# sleep_light.net
KiCad netlist of a schematic drawn in EAGLE
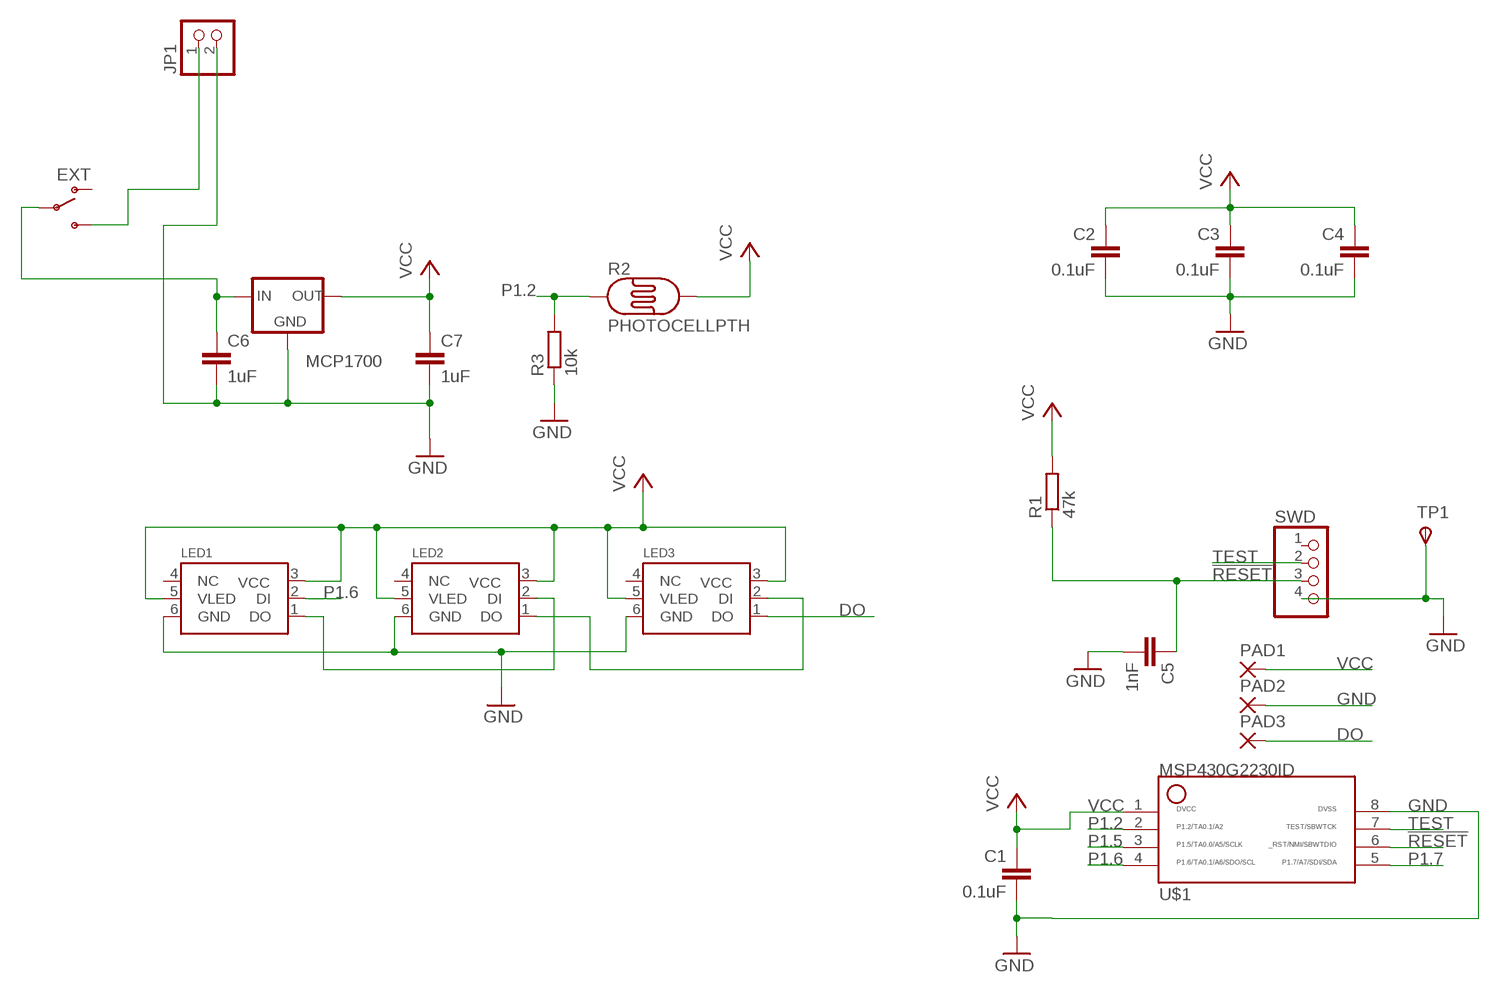
[diagram p0: schematic, sheet 1]

(export (version "E")
  (design (tool "Eeschema 10.0.6"))
  (components
    (comp (ref "C1")
      (value "0.1uF")
      (footprint "eagle-import:C0805")
      (libsource (lib "eagle-import") (part "C-EUC0805"))
    )
    (comp (ref "C2")
      (value "0.1uF")
      (footprint "eagle-import:C0805")
      (libsource (lib "eagle-import") (part "C-EUC0805"))
    )
    (comp (ref "C3")
      (value "0.1uF")
      (footprint "eagle-import:C0805")
      (libsource (lib "eagle-import") (part "C-EUC0805"))
    )
    (comp (ref "C4")
      (value "0.1uF")
      (footprint "eagle-import:C0805")
      (libsource (lib "eagle-import") (part "C-EUC0805"))
    )
    (comp (ref "C5")
      (value "1nF")
      (footprint "eagle-import:C0805")
      (libsource (lib "eagle-import") (part "C-EUC0805"))
    )
    (comp (ref "C6")
      (value "1uF")
      (footprint "eagle-import:C0805")
      (libsource (lib "eagle-import") (part "C-EUC0805"))
    )
    (comp (ref "C7")
      (value "1uF")
      (footprint "eagle-import:C0805")
      (libsource (lib "eagle-import") (part "C-EUC0805"))
    )
    (comp (ref "JP1")
      (value "PINHD-1X2")
      (footprint "eagle-import:1X02")
      (libsource (lib "eagle-import") (part "PINHD-1X2"))
    )
    (comp (ref "LED1")
      (value "5050WS2811W")
      (footprint "eagle-import:RGBLED5050W")
      (libsource (lib "eagle-import") (part "5050WS2811W"))
    )
    (comp (ref "LED2")
      (value "5050WS2811W")
      (footprint "eagle-import:RGBLED5050W")
      (libsource (lib "eagle-import") (part "5050WS2811W"))
    )
    (comp (ref "LED3")
      (value "5050WS2811W")
      (footprint "eagle-import:RGBLED5050W")
      (libsource (lib "eagle-import") (part "5050WS2811W"))
    )
    (comp (ref "MCP1700")
      (value "MCP1700")
      (footprint "eagle-import:SOT-23")
      (libsource (lib "eagle-import") (part "MCP1700SOT-23"))
    )
    (comp (ref "ON")
      (value "EXT")
      (footprint "eagle-import:SWITCH-SPDT")
      (libsource (lib "eagle-import") (part "SWITCH-SPSTPTH"))
    )
    (comp (ref "PAD1")
      (value "SMD2")
      (footprint "eagle-import:SMD1,27-2,54")
      (libsource (lib "eagle-import") (part "SMD2"))
    )
    (comp (ref "PAD2")
      (value "SMD2")
      (footprint "eagle-import:SMD1,27-2,54")
      (libsource (lib "eagle-import") (part "SMD2"))
    )
    (comp (ref "PAD3")
      (value "SMD2")
      (footprint "eagle-import:SMD1,27-2,54")
      (libsource (lib "eagle-import") (part "SMD2"))
    )
    (comp (ref "R1")
      (value "47k")
      (footprint "eagle-import:R0805")
      (libsource (lib "eagle-import") (part "R-EU_R0805"))
    )
    (comp (ref "R2")
      (value "PHOTOCELLPTH")
      (footprint "eagle-import:PHOTOCELL")
      (libsource (lib "eagle-import") (part "PHOTOCELLPTH"))
    )
    (comp (ref "R3")
      (value "10k")
      (footprint "eagle-import:R0805")
      (libsource (lib "eagle-import") (part "R-EU_R0805"))
    )
    (comp (ref "SWD")
      (value "PINHD-1X4")
      (footprint "eagle-import:1X04")
      (libsource (lib "eagle-import") (part "PINHD-1X4"))
    )
    (comp (ref "TP1")
      (value "TPSTP20R")
      (footprint "eagle-import:TP20R")
      (libsource (lib "eagle-import") (part "TPSTP20R"))
    )
    (comp (ref "U$1")
      (value "MSP430G2230ID")
      (footprint "eagle-import:SO08")
      (libsource (lib "eagle-import") (part "MSP430G2230ID"))
    )
  )
  (nets
    (net (code "1") (name "/DO") (class "Default")
      (node (ref "LED3") (pin "1") (pinfunction "DO_1") (pintype "bidirectional"))
      (node (ref "PAD3") (pin "1") (pinfunction "P_1") (pintype "passive"))
    )
    (net (code "2") (name "/P1.2") (class "Default")
      (node (ref "R2") (pin "1") (pinfunction "P$1_1") (pintype "bidirectional"))
      (node (ref "R3") (pin "2") (pinfunction "2_2") (pintype "passive"))
      (node (ref "U$1") (pin "2") (pinfunction "2_2") (pintype "bidirectional"))
    )
    (net (code "3") (name "/P1.5") (class "Default")
      (node (ref "U$1") (pin "3") (pinfunction "3_3") (pintype "bidirectional"))
    )
    (net (code "4") (name "/P1.6") (class "Default")
      (node (ref "LED1") (pin "2") (pinfunction "DI_2") (pintype "bidirectional"))
      (node (ref "U$1") (pin "4") (pinfunction "4_4") (pintype "bidirectional"))
    )
    (net (code "5") (name "/P1.7") (class "Default")
      (node (ref "U$1") (pin "5") (pinfunction "5_5") (pintype "bidirectional"))
    )
    (net (code "6") (name "/TEST") (class "Default")
      (node (ref "SWD") (pin "2") (pinfunction "2_2") (pintype "passive"))
      (node (ref "U$1") (pin "7") (pinfunction "7_7") (pintype "bidirectional"))
    )
    (net (code "7") (name "/~{RESET}") (class "Default")
      (node (ref "C5") (pin "1") (pinfunction "1_1") (pintype "passive"))
      (node (ref "R1") (pin "1") (pinfunction "1_1") (pintype "passive"))
      (node (ref "SWD") (pin "3") (pinfunction "3_3") (pintype "passive"))
      (node (ref "U$1") (pin "6") (pinfunction "6_6") (pintype "bidirectional"))
    )
    (net (code "8") (name "GND") (class "Default")
      (node (ref "C1") (pin "2") (pinfunction "2_2") (pintype "passive"))
      (node (ref "C2") (pin "2") (pinfunction "2_2") (pintype "passive"))
      (node (ref "C3") (pin "2") (pinfunction "2_2") (pintype "passive"))
      (node (ref "C4") (pin "2") (pinfunction "2_2") (pintype "passive"))
      (node (ref "C5") (pin "2") (pinfunction "2_2") (pintype "passive"))
      (node (ref "C6") (pin "2") (pinfunction "2_2") (pintype "passive"))
      (node (ref "C7") (pin "2") (pinfunction "2_2") (pintype "passive"))
      (node (ref "JP1") (pin "2") (pinfunction "2_2") (pintype "passive"))
      (node (ref "LED1") (pin "6") (pinfunction "GND_6") (pintype "bidirectional"))
      (node (ref "LED2") (pin "6") (pinfunction "GND_6") (pintype "bidirectional"))
      (node (ref "LED3") (pin "6") (pinfunction "GND_6") (pintype "bidirectional"))
      (node (ref "MCP1700") (pin "1") (pinfunction "GND_1") (pintype "input"))
      (node (ref "PAD2") (pin "1") (pinfunction "P_1") (pintype "passive"))
      (node (ref "R3") (pin "1") (pinfunction "1_1") (pintype "passive"))
      (node (ref "SWD") (pin "4") (pinfunction "4_4") (pintype "passive"))
      (node (ref "TP1") (pin "TP") (pinfunction "PP_TP") (pintype "input"))
      (node (ref "U$1") (pin "8") (pinfunction "8_8") (pintype "power_in"))
    )
    (net (code "9") (name "Net-(LED1-DO)") (class "Default")
      (node (ref "LED1") (pin "1") (pinfunction "DO_1") (pintype "bidirectional"))
      (node (ref "LED2") (pin "2") (pinfunction "DI_2") (pintype "bidirectional"))
    )
    (net (code "10") (name "Net-(LED2-DO)") (class "Default")
      (node (ref "LED2") (pin "1") (pinfunction "DO_1") (pintype "bidirectional"))
      (node (ref "LED3") (pin "2") (pinfunction "DI_2") (pintype "bidirectional"))
    )
    (net (code "11") (name "Net-(MCP1700-IN)") (class "Default")
      (node (ref "C6") (pin "1") (pinfunction "1_1") (pintype "passive"))
      (node (ref "MCP1700") (pin "3") (pinfunction "IN_3") (pintype "input"))
      (node (ref "ON") (pin "2") (pinfunction "P_2") (pintype "passive"))
    )
    (net (code "12") (name "Net-(ON-S)") (class "Default")
      (node (ref "JP1") (pin "1") (pinfunction "1_1") (pintype "passive"))
      (node (ref "ON") (pin "3") (pinfunction "S_3") (pintype "passive"))
    )
    (net (code "13") (name "VCC") (class "Default")
      (node (ref "C1") (pin "1") (pinfunction "1_1") (pintype "passive"))
      (node (ref "C2") (pin "1") (pinfunction "1_1") (pintype "passive"))
      (node (ref "C3") (pin "1") (pinfunction "1_1") (pintype "passive"))
      (node (ref "C4") (pin "1") (pinfunction "1_1") (pintype "passive"))
      (node (ref "C7") (pin "1") (pinfunction "1_1") (pintype "passive"))
      (node (ref "LED1") (pin "3") (pinfunction "VCC_3") (pintype "bidirectional"))
      (node (ref "LED1") (pin "5") (pinfunction "VLED_5") (pintype "bidirectional"))
      (node (ref "LED2") (pin "3") (pinfunction "VCC_3") (pintype "bidirectional"))
      (node (ref "LED2") (pin "5") (pinfunction "VLED_5") (pintype "bidirectional"))
      (node (ref "LED3") (pin "3") (pinfunction "VCC_3") (pintype "bidirectional"))
      (node (ref "LED3") (pin "5") (pinfunction "VLED_5") (pintype "bidirectional"))
      (node (ref "MCP1700") (pin "2") (pinfunction "OUT_2") (pintype "passive"))
      (node (ref "PAD1") (pin "1") (pinfunction "P_1") (pintype "passive"))
      (node (ref "R1") (pin "2") (pinfunction "2_2") (pintype "passive"))
      (node (ref "R2") (pin "2") (pinfunction "P$2_2") (pintype "bidirectional"))
      (node (ref "U$1") (pin "1") (pinfunction "1_1") (pintype "power_in"))
    )
    (net (code "14") (name "unconnected-(LED1-NC-Pad4)") (class "Default")
      (node (ref "LED1") (pin "4") (pinfunction "NC_4") (pintype "bidirectional"))
    )
    (net (code "15") (name "unconnected-(LED2-NC-Pad4)") (class "Default")
      (node (ref "LED2") (pin "4") (pinfunction "NC_4") (pintype "bidirectional"))
    )
    (net (code "16") (name "unconnected-(LED3-NC-Pad4)") (class "Default")
      (node (ref "LED3") (pin "4") (pinfunction "NC_4") (pintype "bidirectional"))
    )
    (net (code "17") (name "unconnected-(ON-O-Pad1)") (class "Default")
      (node (ref "ON") (pin "1") (pinfunction "O_1") (pintype "passive"))
    )
    (net (code "18") (name "unconnected-(SWD-Pad1)") (class "Default")
      (node (ref "SWD") (pin "1") (pinfunction "1_1") (pintype "passive"))
    )
  )
)
